# Arduino_mount.net
KiCad netlist of a schematic drawn in EAGLE
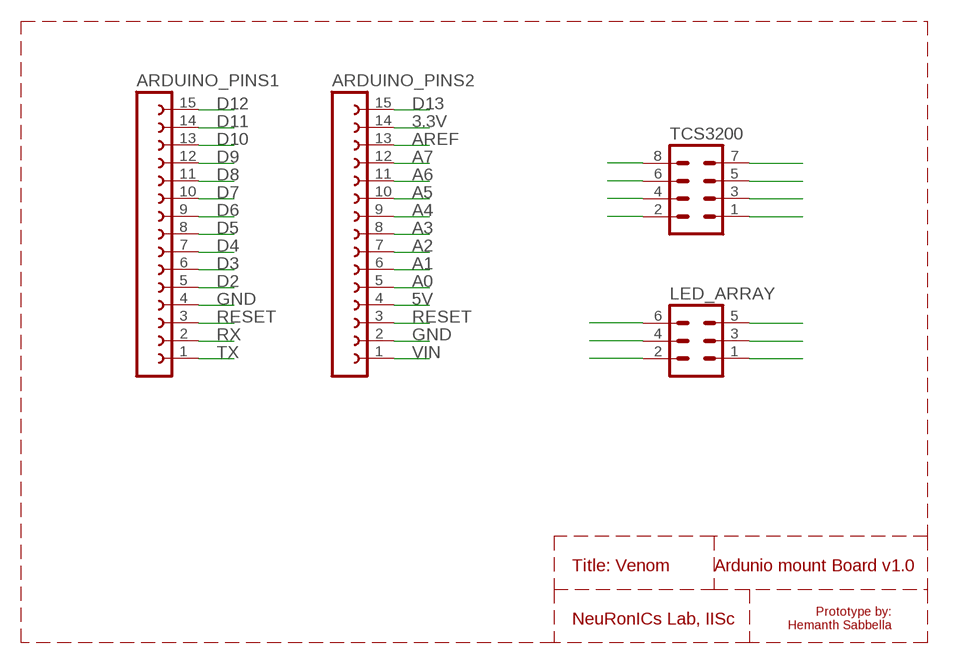
[diagram p0: schematic, sheet 1]

(export (version "E")
  (design (tool "Eeschema 10.0.6"))
  (components
    (comp (ref "ARDUINO_PINS1")
      (value "FE15-1")
      (footprint "eagle-import:FE15")
      (libsource (lib "eagle-import") (part "FE15-1"))
    )
    (comp (ref "ARDUINO_PINS2")
      (value "FE15-1")
      (footprint "eagle-import:FE15")
      (libsource (lib "eagle-import") (part "FE15-1"))
    )
    (comp (ref "LED_ARRAY")
      (value "MA03-2")
      (footprint "eagle-import:MA03-2")
      (libsource (lib "eagle-import") (part "MA03-2"))
    )
    (comp (ref "TCS3200")
      (value "MA04-2")
      (footprint "eagle-import:MA04-2")
      (libsource (lib "eagle-import") (part "MA04-2"))
    )
  )
  (nets
    (net (code "1") (name "/3.3V") (class "Default")
      (node (ref "ARDUINO_PINS2") (pin "14") (pinfunction "14_14") (pintype "passive"))
    )
    (net (code "2") (name "/5V") (class "Default")
      (node (ref "ARDUINO_PINS2") (pin "4") (pinfunction "4_4") (pintype "passive"))
    )
    (net (code "3") (name "/A0") (class "Default")
      (node (ref "ARDUINO_PINS2") (pin "5") (pinfunction "5_5") (pintype "passive"))
    )
    (net (code "4") (name "/A1") (class "Default")
      (node (ref "ARDUINO_PINS2") (pin "6") (pinfunction "6_6") (pintype "passive"))
    )
    (net (code "5") (name "/A2") (class "Default")
      (node (ref "ARDUINO_PINS2") (pin "7") (pinfunction "7_7") (pintype "passive"))
    )
    (net (code "6") (name "/A3") (class "Default")
      (node (ref "ARDUINO_PINS2") (pin "8") (pinfunction "8_8") (pintype "passive"))
    )
    (net (code "7") (name "/A4") (class "Default")
      (node (ref "ARDUINO_PINS2") (pin "9") (pinfunction "9_9") (pintype "passive"))
    )
    (net (code "8") (name "/A5") (class "Default")
      (node (ref "ARDUINO_PINS2") (pin "10") (pinfunction "10_10") (pintype "passive"))
    )
    (net (code "9") (name "/A6") (class "Default")
      (node (ref "ARDUINO_PINS2") (pin "11") (pinfunction "11_11") (pintype "passive"))
    )
    (net (code "10") (name "/A7") (class "Default")
      (node (ref "ARDUINO_PINS2") (pin "12") (pinfunction "12_12") (pintype "passive"))
    )
    (net (code "11") (name "/AREF") (class "Default")
      (node (ref "ARDUINO_PINS2") (pin "13") (pinfunction "13_13") (pintype "passive"))
    )
    (net (code "12") (name "/D2") (class "Default")
      (node (ref "ARDUINO_PINS1") (pin "5") (pinfunction "5_5") (pintype "passive"))
    )
    (net (code "13") (name "/D3") (class "Default")
      (node (ref "ARDUINO_PINS1") (pin "6") (pinfunction "6_6") (pintype "passive"))
    )
    (net (code "14") (name "/D4") (class "Default")
      (node (ref "ARDUINO_PINS1") (pin "7") (pinfunction "7_7") (pintype "passive"))
    )
    (net (code "15") (name "/D5") (class "Default")
      (node (ref "ARDUINO_PINS1") (pin "8") (pinfunction "8_8") (pintype "passive"))
    )
    (net (code "16") (name "/D6") (class "Default")
      (node (ref "ARDUINO_PINS1") (pin "9") (pinfunction "9_9") (pintype "passive"))
    )
    (net (code "17") (name "/D7") (class "Default")
      (node (ref "ARDUINO_PINS1") (pin "10") (pinfunction "10_10") (pintype "passive"))
    )
    (net (code "18") (name "/D8") (class "Default")
      (node (ref "ARDUINO_PINS1") (pin "11") (pinfunction "11_11") (pintype "passive"))
    )
    (net (code "19") (name "/D9") (class "Default")
      (node (ref "ARDUINO_PINS1") (pin "12") (pinfunction "12_12") (pintype "passive"))
    )
    (net (code "20") (name "/D10") (class "Default")
      (node (ref "ARDUINO_PINS1") (pin "13") (pinfunction "13_13") (pintype "passive"))
    )
    (net (code "21") (name "/D11") (class "Default")
      (node (ref "ARDUINO_PINS1") (pin "14") (pinfunction "14_14") (pintype "passive"))
    )
    (net (code "22") (name "/D12") (class "Default")
      (node (ref "ARDUINO_PINS1") (pin "15") (pinfunction "15_15") (pintype "passive"))
    )
    (net (code "23") (name "/D13") (class "Default")
      (node (ref "ARDUINO_PINS2") (pin "15") (pinfunction "15_15") (pintype "passive"))
    )
    (net (code "24") (name "/GND") (class "Default")
      (node (ref "ARDUINO_PINS1") (pin "4") (pinfunction "4_4") (pintype "passive"))
      (node (ref "ARDUINO_PINS2") (pin "2") (pinfunction "2_2") (pintype "passive"))
    )
    (net (code "25") (name "/RESET") (class "Default")
      (node (ref "ARDUINO_PINS1") (pin "3") (pinfunction "3_3") (pintype "passive"))
      (node (ref "ARDUINO_PINS2") (pin "3") (pinfunction "3_3") (pintype "passive"))
    )
    (net (code "26") (name "/RX") (class "Default")
      (node (ref "ARDUINO_PINS1") (pin "2") (pinfunction "2_2") (pintype "passive"))
    )
    (net (code "27") (name "/TX") (class "Default")
      (node (ref "ARDUINO_PINS1") (pin "1") (pinfunction "1_1") (pintype "passive"))
    )
    (net (code "28") (name "/VIN") (class "Default")
      (node (ref "ARDUINO_PINS2") (pin "1") (pinfunction "1_1") (pintype "passive"))
    )
    (net (code "29") (name "unconnected-(LED_ARRAY-Pad1)") (class "Default")
      (node (ref "LED_ARRAY") (pin "1") (pinfunction "1_1") (pintype "passive"))
    )
    (net (code "30") (name "unconnected-(LED_ARRAY-Pad2)") (class "Default")
      (node (ref "LED_ARRAY") (pin "2") (pinfunction "2_2") (pintype "passive"))
    )
    (net (code "31") (name "unconnected-(LED_ARRAY-Pad3)") (class "Default")
      (node (ref "LED_ARRAY") (pin "3") (pinfunction "3_3") (pintype "passive"))
    )
    (net (code "32") (name "unconnected-(LED_ARRAY-Pad4)") (class "Default")
      (node (ref "LED_ARRAY") (pin "4") (pinfunction "4_4") (pintype "passive"))
    )
    (net (code "33") (name "unconnected-(LED_ARRAY-Pad5)") (class "Default")
      (node (ref "LED_ARRAY") (pin "5") (pinfunction "5_5") (pintype "passive"))
    )
    (net (code "34") (name "unconnected-(LED_ARRAY-Pad6)") (class "Default")
      (node (ref "LED_ARRAY") (pin "6") (pinfunction "6_6") (pintype "passive"))
    )
    (net (code "35") (name "unconnected-(TCS3200-Pad1)") (class "Default")
      (node (ref "TCS3200") (pin "1") (pinfunction "1_1") (pintype "passive"))
    )
    (net (code "36") (name "unconnected-(TCS3200-Pad2)") (class "Default")
      (node (ref "TCS3200") (pin "2") (pinfunction "2_2") (pintype "passive"))
    )
    (net (code "37") (name "unconnected-(TCS3200-Pad3)") (class "Default")
      (node (ref "TCS3200") (pin "3") (pinfunction "3_3") (pintype "passive"))
    )
    (net (code "38") (name "unconnected-(TCS3200-Pad4)") (class "Default")
      (node (ref "TCS3200") (pin "4") (pinfunction "4_4") (pintype "passive"))
    )
    (net (code "39") (name "unconnected-(TCS3200-Pad5)") (class "Default")
      (node (ref "TCS3200") (pin "5") (pinfunction "5_5") (pintype "passive"))
    )
    (net (code "40") (name "unconnected-(TCS3200-Pad6)") (class "Default")
      (node (ref "TCS3200") (pin "6") (pinfunction "6_6") (pintype "passive"))
    )
    (net (code "41") (name "unconnected-(TCS3200-Pad7)") (class "Default")
      (node (ref "TCS3200") (pin "7") (pinfunction "7_7") (pintype "passive"))
    )
    (net (code "42") (name "unconnected-(TCS3200-Pad8)") (class "Default")
      (node (ref "TCS3200") (pin "8") (pinfunction "8_8") (pintype "passive"))
    )
  )
)
